# ledboard.net
KiCad netlist of a schematic drawn in EAGLE
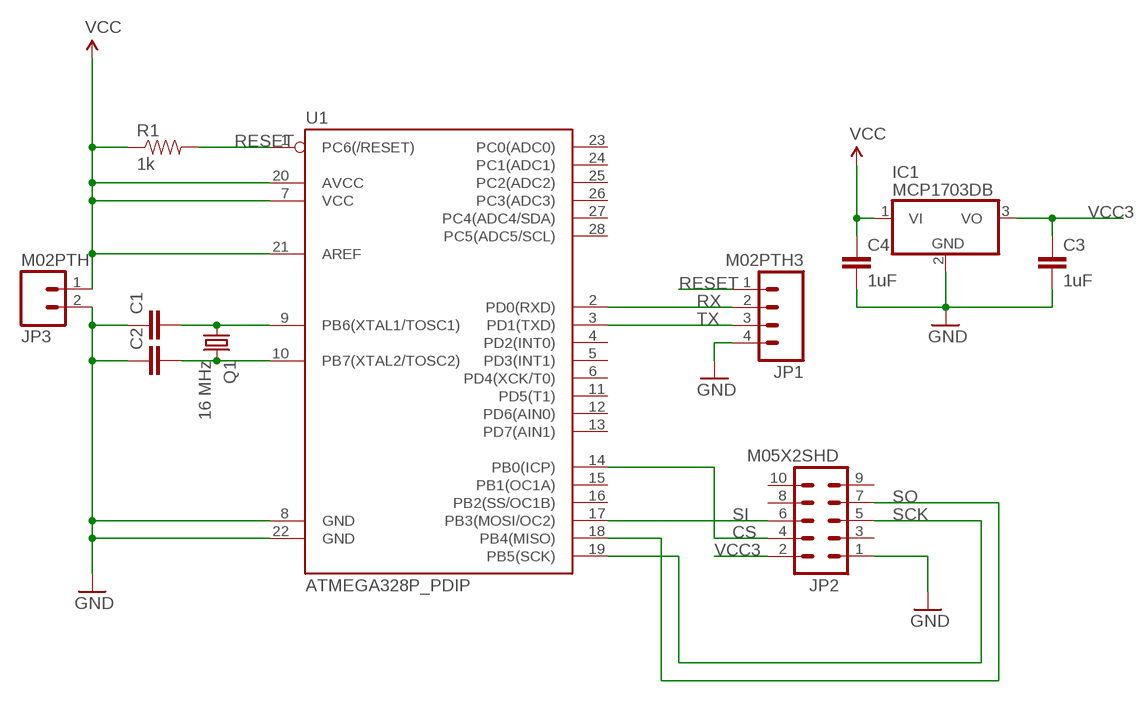
[diagram p0: schematic, sheet 1]

(export (version "E")
  (design (tool "Eeschema 10.0.6"))
  (components
    (comp (ref "C1")
      (value "CAP0805")
      (footprint "eagle-import:0805")
      (libsource (lib "eagle-import") (part "CAP0805"))
    )
    (comp (ref "C2")
      (value "CAP0805")
      (footprint "eagle-import:0805")
      (libsource (lib "eagle-import") (part "CAP0805"))
    )
    (comp (ref "C3")
      (value "1uF")
      (footprint "eagle-import:0805")
      (libsource (lib "eagle-import") (part "CAP0805"))
    )
    (comp (ref "C4")
      (value "1uF")
      (footprint "eagle-import:0805")
      (libsource (lib "eagle-import") (part "CAP0805"))
    )
    (comp (ref "IC1")
      (value "MCP1703DB")
      (footprint "eagle-import:SOT223")
      (libsource (lib "eagle-import") (part "MCP1703DB"))
    )
    (comp (ref "JP1")
      (value "M02PTH3")
      (footprint "eagle-import:1X04_NO_SILK")
      (libsource (lib "eagle-import") (part "M041X04_NO_SILK"))
    )
    (comp (ref "JP2")
      (value "M05X2SHD")
      (footprint "eagle-import:2X5-SHROUDED")
      (libsource (lib "eagle-import") (part "M05X2SHD"))
    )
    (comp (ref "JP3")
      (value "M02PTH")
      (footprint "eagle-import:1X02")
      (libsource (lib "eagle-import") (part "M02PTH"))
    )
    (comp (ref "Q1")
      (value "16 MHz")
      (footprint "eagle-import:HC49UP")
      (libsource (lib "eagle-import") (part "CRYSTALSMD"))
    )
    (comp (ref "R1")
      (value "1k")
      (footprint "eagle-import:0805")
      (libsource (lib "eagle-import") (part "RESISTOR0805-RES"))
    )
    (comp (ref "U1")
      (value "ATMEGA328P_PDIP")
      (footprint "eagle-import:DIL28-3")
      (libsource (lib "eagle-import") (part "ATMEGA328P_PDIP"))
    )
  )
  (nets
    (net (code "1") (name "/CS") (class "Default")
      (node (ref "JP2") (pin "4") (pinfunction "4_4") (pintype "passive"))
      (node (ref "U1") (pin "14") (pinfunction "PB0(ICP)_14") (pintype "bidirectional"))
    )
    (net (code "2") (name "/RESET") (class "Default")
      (node (ref "JP1") (pin "1") (pinfunction "1_1") (pintype "passive"))
      (node (ref "R1") (pin "2") (pinfunction "2_2") (pintype "passive"))
      (node (ref "U1") (pin "1") (pinfunction "PC6(/RESET)_1") (pintype "bidirectional"))
    )
    (net (code "3") (name "/RX") (class "Default")
      (node (ref "JP1") (pin "2") (pinfunction "2_2") (pintype "passive"))
      (node (ref "U1") (pin "2") (pinfunction "PD0(RXD)_2") (pintype "bidirectional"))
    )
    (net (code "4") (name "/SCK") (class "Default")
      (node (ref "JP2") (pin "5") (pinfunction "5_5") (pintype "passive"))
      (node (ref "U1") (pin "19") (pinfunction "PB5(SCK)_19") (pintype "bidirectional"))
    )
    (net (code "5") (name "/SI") (class "Default")
      (node (ref "JP2") (pin "6") (pinfunction "6_6") (pintype "passive"))
      (node (ref "U1") (pin "17") (pinfunction "PB3(MOSI/OC2)_17") (pintype "bidirectional"))
    )
    (net (code "6") (name "/SO") (class "Default")
      (node (ref "JP2") (pin "7") (pinfunction "7_7") (pintype "passive"))
      (node (ref "U1") (pin "18") (pinfunction "PB4(MISO)_18") (pintype "bidirectional"))
    )
    (net (code "7") (name "/TX") (class "Default")
      (node (ref "JP1") (pin "3") (pinfunction "3_3") (pintype "passive"))
      (node (ref "U1") (pin "3") (pinfunction "PD1(TXD)_3") (pintype "bidirectional"))
    )
    (net (code "8") (name "/VCC3") (class "Default")
      (node (ref "C3") (pin "1") (pinfunction "1_1") (pintype "passive"))
      (node (ref "IC1") (pin "3") (pinfunction "VO_3") (pintype "passive"))
      (node (ref "JP2") (pin "2") (pinfunction "2_2") (pintype "passive"))
    )
    (net (code "9") (name "GND") (class "Default")
      (node (ref "C1") (pin "1") (pinfunction "1_1") (pintype "passive"))
      (node (ref "C2") (pin "1") (pinfunction "1_1") (pintype "passive"))
      (node (ref "C3") (pin "2") (pinfunction "2_2") (pintype "passive"))
      (node (ref "C4") (pin "2") (pinfunction "2_2") (pintype "passive"))
      (node (ref "IC1") (pin "2") (pinfunction "GND_2") (pintype "passive"))
      (node (ref "JP1") (pin "4") (pinfunction "4_4") (pintype "passive"))
      (node (ref "JP2") (pin "1") (pinfunction "1_1") (pintype "passive"))
      (node (ref "JP3") (pin "2") (pinfunction "2_2") (pintype "passive"))
      (node (ref "U1") (pin "22") (pinfunction "GND_22") (pintype "bidirectional"))
      (node (ref "U1") (pin "8") (pinfunction "GND_8") (pintype "bidirectional"))
    )
    (net (code "10") (name "Net-(U1-PB6(XTAL1{slash}TOSC1))") (class "Default")
      (node (ref "C1") (pin "2") (pinfunction "2_2") (pintype "passive"))
      (node (ref "Q1") (pin "1") (pinfunction "1_1") (pintype "passive"))
      (node (ref "U1") (pin "9") (pinfunction "PB6(XTAL1/TOSC1)_9") (pintype "bidirectional"))
    )
    (net (code "11") (name "Net-(U1-PB7(XTAL2{slash}TOSC2))") (class "Default")
      (node (ref "C2") (pin "2") (pinfunction "2_2") (pintype "passive"))
      (node (ref "Q1") (pin "2") (pinfunction "2_2") (pintype "passive"))
      (node (ref "U1") (pin "10") (pinfunction "PB7(XTAL2/TOSC2)_10") (pintype "bidirectional"))
    )
    (net (code "12") (name "VCC") (class "Default")
      (node (ref "C4") (pin "1") (pinfunction "1_1") (pintype "passive"))
      (node (ref "IC1") (pin "1") (pinfunction "VI_1") (pintype "input"))
      (node (ref "JP3") (pin "1") (pinfunction "1_1") (pintype "passive"))
      (node (ref "R1") (pin "1") (pinfunction "1_1") (pintype "passive"))
      (node (ref "U1") (pin "20") (pinfunction "AVCC_20") (pintype "bidirectional"))
      (node (ref "U1") (pin "21") (pinfunction "AREF_21") (pintype "bidirectional"))
      (node (ref "U1") (pin "7") (pinfunction "VCC_7") (pintype "bidirectional"))
    )
    (net (code "13") (name "unconnected-(JP2-Pad3)") (class "Default")
      (node (ref "JP2") (pin "3") (pinfunction "3_3") (pintype "passive"))
    )
    (net (code "14") (name "unconnected-(JP2-Pad8)") (class "Default")
      (node (ref "JP2") (pin "8") (pinfunction "8_8") (pintype "passive"))
    )
    (net (code "15") (name "unconnected-(JP2-Pad9)") (class "Default")
      (node (ref "JP2") (pin "9") (pinfunction "9_9") (pintype "passive"))
    )
    (net (code "16") (name "unconnected-(JP2-Pad10)") (class "Default")
      (node (ref "JP2") (pin "10") (pinfunction "10_10") (pintype "passive"))
    )
    (net (code "17") (name "unconnected-(U1-PB1(OC1A)-Pad15)") (class "Default")
      (node (ref "U1") (pin "15") (pinfunction "PB1(OC1A)_15") (pintype "bidirectional"))
    )
    (net (code "18") (name "unconnected-(U1-PB2(SS{slash}OC1B)-Pad16)") (class "Default")
      (node (ref "U1") (pin "16") (pinfunction "PB2(SS/OC1B)_16") (pintype "bidirectional"))
    )
    (net (code "19") (name "unconnected-(U1-PC0(ADC0)-Pad23)") (class "Default")
      (node (ref "U1") (pin "23") (pinfunction "PC0(ADC0)_23") (pintype "bidirectional"))
    )
    (net (code "20") (name "unconnected-(U1-PC1(ADC1)-Pad24)") (class "Default")
      (node (ref "U1") (pin "24") (pinfunction "PC1(ADC1)_24") (pintype "bidirectional"))
    )
    (net (code "21") (name "unconnected-(U1-PC2(ADC2)-Pad25)") (class "Default")
      (node (ref "U1") (pin "25") (pinfunction "PC2(ADC2)_25") (pintype "bidirectional"))
    )
    (net (code "22") (name "unconnected-(U1-PC3(ADC3)-Pad26)") (class "Default")
      (node (ref "U1") (pin "26") (pinfunction "PC3(ADC3)_26") (pintype "bidirectional"))
    )
    (net (code "23") (name "unconnected-(U1-PC4(ADC4{slash}SDA)-Pad27)") (class "Default")
      (node (ref "U1") (pin "27") (pinfunction "PC4(ADC4/SDA)_27") (pintype "bidirectional"))
    )
    (net (code "24") (name "unconnected-(U1-PC5(ADC5{slash}SCL)-Pad28)") (class "Default")
      (node (ref "U1") (pin "28") (pinfunction "PC5(ADC5/SCL)_28") (pintype "bidirectional"))
    )
    (net (code "25") (name "unconnected-(U1-PD2(INT0)-Pad4)") (class "Default")
      (node (ref "U1") (pin "4") (pinfunction "PD2(INT0)_4") (pintype "bidirectional"))
    )
    (net (code "26") (name "unconnected-(U1-PD3(INT1)-Pad5)") (class "Default")
      (node (ref "U1") (pin "5") (pinfunction "PD3(INT1)_5") (pintype "bidirectional"))
    )
    (net (code "27") (name "unconnected-(U1-PD4(XCK{slash}T0)-Pad6)") (class "Default")
      (node (ref "U1") (pin "6") (pinfunction "PD4(XCK/T0)_6") (pintype "bidirectional"))
    )
    (net (code "28") (name "unconnected-(U1-PD5(T1)-Pad11)") (class "Default")
      (node (ref "U1") (pin "11") (pinfunction "PD5(T1)_11") (pintype "bidirectional"))
    )
    (net (code "29") (name "unconnected-(U1-PD6(AIN0)-Pad12)") (class "Default")
      (node (ref "U1") (pin "12") (pinfunction "PD6(AIN0)_12") (pintype "bidirectional"))
    )
    (net (code "30") (name "unconnected-(U1-PD7(AIN1)-Pad13)") (class "Default")
      (node (ref "U1") (pin "13") (pinfunction "PD7(AIN1)_13") (pintype "bidirectional"))
    )
  )
)
